# sb-sonata-led.net
KiCad netlist of a schematic drawn in Altium Designer
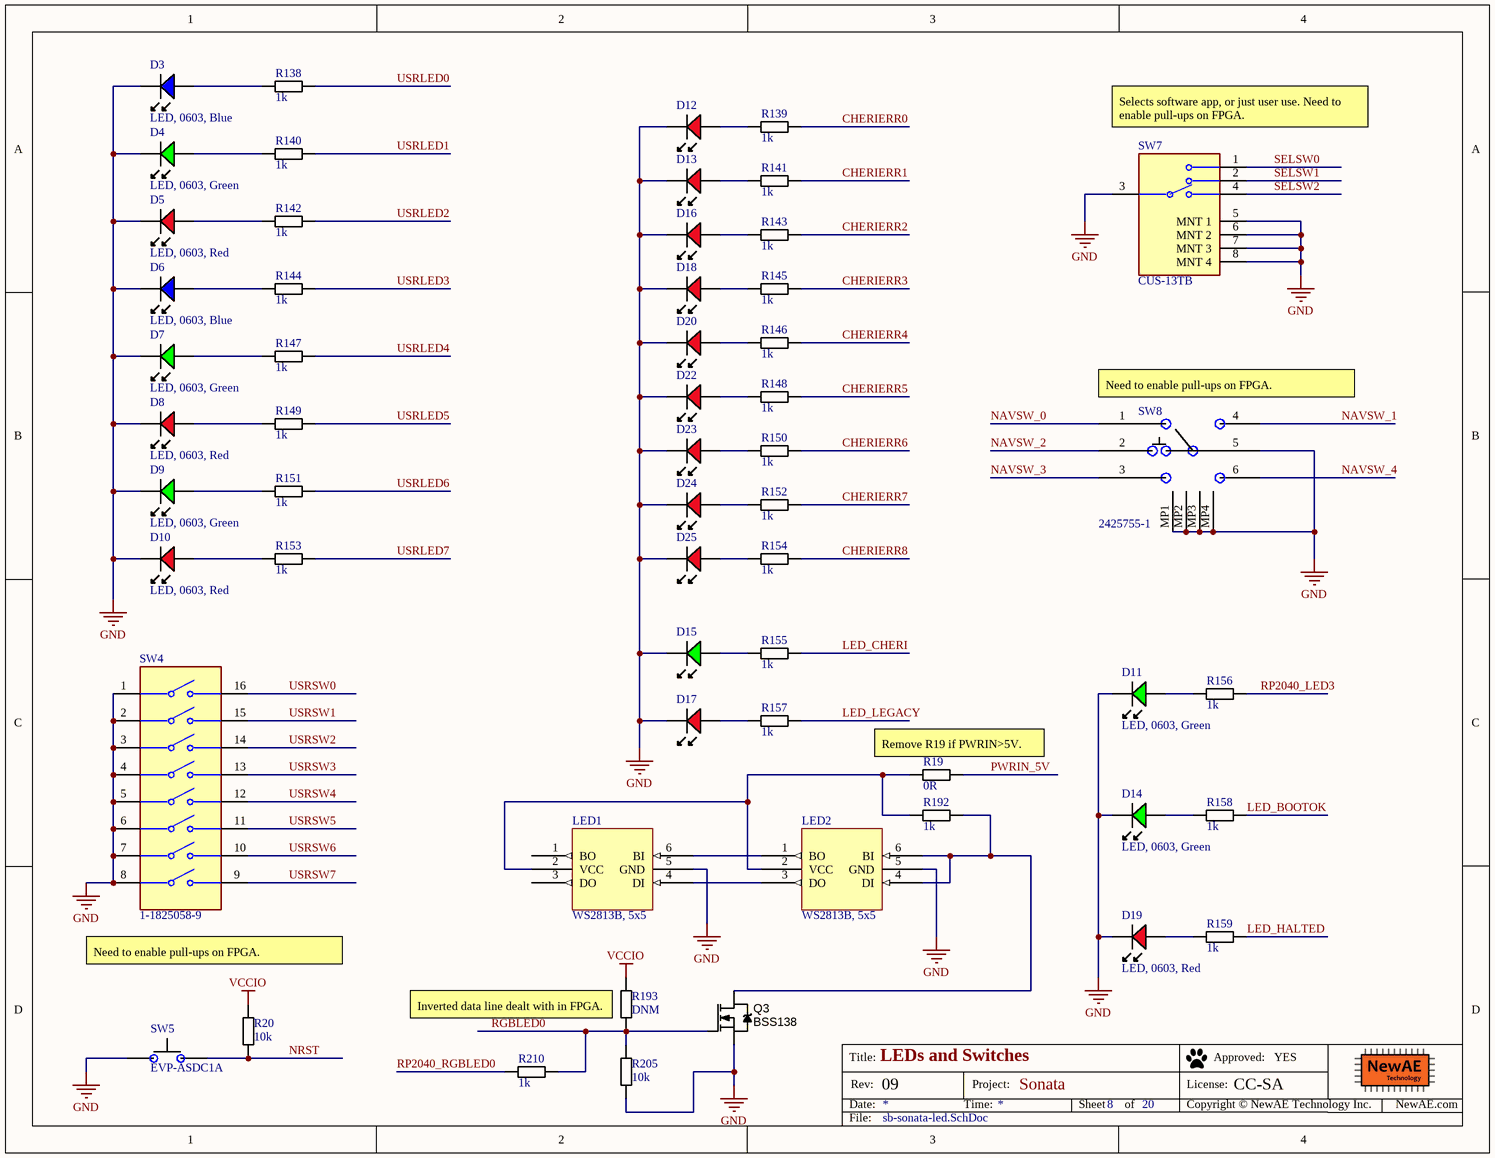
[diagram p0: sb-sonata-led.SchDoc]

(export (version "E")
  (design (tool "Eeschema 10.0.6"))
  (components
    (comp (ref "D3")
      (value "LED, 0603, Blue")
      (footprint "LED-0603-BLUE")
      (description "Chip LED, Blue")
      (fields (field (name "PART NUMBER") "LEDCHIP_0603_BLUE"))
      (libsource (lib "NewAE_AltiumLib") (part "LED_BLUE"))
    )
    (comp (ref "D4")
      (value "LED, 0603, Green")
      (footprint "LED-0603-GREEN")
      (description "Chip LED, Green")
      (fields (field (name "PART NUMBER") "LEDCHIP_0603_GREEN"))
      (libsource (lib "NewAE_AltiumLib") (part "LED_GREEN"))
    )
    (comp (ref "D5")
      (value "LED, 0603, Red")
      (footprint "LED-0603-RED")
      (description "Chip LED, Red")
      (fields (field (name "PART NUMBER") "LEDCHIP_0603_RED"))
      (libsource (lib "NewAE_AltiumLib") (part "LED_RED"))
    )
    (comp (ref "D6")
      (value "LED, 0603, Blue")
      (footprint "LED-0603-BLUE")
      (description "Chip LED, Blue")
      (fields (field (name "PART NUMBER") "LEDCHIP_0603_BLUE"))
      (libsource (lib "NewAE_AltiumLib") (part "LED_BLUE"))
    )
    (comp (ref "D7")
      (value "LED, 0603, Green")
      (footprint "LED-0603-GREEN")
      (description "Chip LED, Green")
      (fields (field (name "PART NUMBER") "LEDCHIP_0603_GREEN"))
      (libsource (lib "NewAE_AltiumLib") (part "LED_GREEN"))
    )
    (comp (ref "D8")
      (value "LED, 0603, Red")
      (footprint "LED-0603-RED")
      (description "Chip LED, Red")
      (fields (field (name "PART NUMBER") "LEDCHIP_0603_RED"))
      (libsource (lib "NewAE_AltiumLib") (part "LED_RED"))
    )
    (comp (ref "D9")
      (value "LED, 0603, Green")
      (footprint "LED-0603-GREEN")
      (description "Chip LED, Green")
      (fields (field (name "PART NUMBER") "LEDCHIP_0603_GREEN"))
      (libsource (lib "NewAE_AltiumLib") (part "LED_GREEN"))
    )
    (comp (ref "D10")
      (value "LED, 0603, Red")
      (footprint "LED-0603-RED")
      (description "Chip LED, Red")
      (fields (field (name "PART NUMBER") "LEDCHIP_0603_RED"))
      (libsource (lib "NewAE_AltiumLib") (part "LED_RED"))
    )
    (comp (ref "D11")
      (value "LED, 0603, Green")
      (footprint "LED-0603-GREEN")
      (description "Chip LED, Green")
      (fields (field (name "PART NUMBER") "LEDCHIP_0603_GREEN"))
      (libsource (lib "NewAE_AltiumLib") (part "LED_GREEN"))
    )
    (comp (ref "D12")
      (value "LED, 0603, Red")
      (footprint "LED-0603-RED")
      (description "Chip LED, Red")
      (fields (field (name "PART NUMBER") "LEDCHIP_0603_RED"))
      (libsource (lib "NewAE_AltiumLib") (part "LED_RED"))
    )
    (comp (ref "D13")
      (value "LED, 0603, Red")
      (footprint "LED-0603-RED")
      (description "Chip LED, Red")
      (fields (field (name "PART NUMBER") "LEDCHIP_0603_RED"))
      (libsource (lib "NewAE_AltiumLib") (part "LED_RED"))
    )
    (comp (ref "D14")
      (value "LED, 0603, Green")
      (footprint "LED-0603-GREEN")
      (description "Chip LED, Green")
      (fields (field (name "PART NUMBER") "LEDCHIP_0603_GREEN"))
      (libsource (lib "NewAE_AltiumLib") (part "LED_GREEN"))
    )
    (comp (ref "D15")
      (value "LED, 0603, Green")
      (footprint "LED-0603-GREEN")
      (description "Chip LED, Green")
      (fields (field (name "PART NUMBER") "LEDCHIP_0603_GREEN"))
      (libsource (lib "NewAE_AltiumLib") (part "LED_GREEN"))
    )
    (comp (ref "D16")
      (value "LED, 0603, Red")
      (footprint "LED-0603-RED")
      (description "Chip LED, Red")
      (fields (field (name "PART NUMBER") "LEDCHIP_0603_RED"))
      (libsource (lib "NewAE_AltiumLib") (part "LED_RED"))
    )
    (comp (ref "D17")
      (value "LED, 0603, Red")
      (footprint "LED-0603-RED")
      (description "Chip LED, Red")
      (fields (field (name "PART NUMBER") "LEDCHIP_0603_RED"))
      (libsource (lib "NewAE_AltiumLib") (part "LED_RED"))
    )
    (comp (ref "D18")
      (value "LED, 0603, Red")
      (footprint "LED-0603-RED")
      (description "Chip LED, Red")
      (fields (field (name "PART NUMBER") "LEDCHIP_0603_RED"))
      (libsource (lib "NewAE_AltiumLib") (part "LED_RED"))
    )
    (comp (ref "D19")
      (value "LED, 0603, Red")
      (footprint "LED-0603-RED")
      (description "Chip LED, Red")
      (fields (field (name "PART NUMBER") "LEDCHIP_0603_RED"))
      (libsource (lib "NewAE_AltiumLib") (part "LED_RED"))
    )
    (comp (ref "D20")
      (value "LED, 0603, Red")
      (footprint "LED-0603-RED")
      (description "Chip LED, Red")
      (fields (field (name "PART NUMBER") "LEDCHIP_0603_RED"))
      (libsource (lib "NewAE_AltiumLib") (part "LED_RED"))
    )
    (comp (ref "D22")
      (value "LED, 0603, Red")
      (footprint "LED-0603-RED")
      (description "Chip LED, Red")
      (fields (field (name "PART NUMBER") "LEDCHIP_0603_RED"))
      (libsource (lib "NewAE_AltiumLib") (part "LED_RED"))
    )
    (comp (ref "D23")
      (value "LED, 0603, Red")
      (footprint "LED-0603-RED")
      (description "Chip LED, Red")
      (fields (field (name "PART NUMBER") "LEDCHIP_0603_RED"))
      (libsource (lib "NewAE_AltiumLib") (part "LED_RED"))
    )
    (comp (ref "D24")
      (value "LED, 0603, Red")
      (footprint "LED-0603-RED")
      (description "Chip LED, Red")
      (fields (field (name "PART NUMBER") "LEDCHIP_0603_RED"))
      (libsource (lib "NewAE_AltiumLib") (part "LED_RED"))
    )
    (comp (ref "D25")
      (value "LED, 0603, Red")
      (footprint "LED-0603-RED")
      (description "Chip LED, Red")
      (fields (field (name "PART NUMBER") "LEDCHIP_0603_RED"))
      (libsource (lib "NewAE_AltiumLib") (part "LED_RED"))
    )
    (comp (ref "LED1")
      (value "WS2813B, 5x5")
      (footprint "WS2813B_5x5")
      (description "WS2813B, 5x5 SMD Neopixel")
      (fields (field (name "PART NUMBER") "WS2813B_5x5"))
      (libsource (lib "NewAE_AltiumLib") (part "WS2813B"))
    )
    (comp (ref "LED2")
      (value "WS2813B, 5x5")
      (footprint "WS2813B_5x5")
      (description "WS2813B, 5x5 SMD Neopixel")
      (fields (field (name "PART NUMBER") "WS2813B_5x5"))
      (libsource (lib "NewAE_AltiumLib") (part "WS2813B"))
    )
    (comp (ref "Q3")
      (value "BSS138")
      (footprint "SOT95P245X110-3M")
      (description "MOSFET N-CH 30V 2.2A SOT23-3")
      (libsource (lib "NewAE_AltiumLib") (part "MOSFET_N_GSD"))
    )
    (comp (ref "R19")
      (value "0R")
      (footprint "RESC1608X55N")
      (description "0R, 0603, 1/10W")
      (fields (field (name "PART NUMBER") "RCHIP-0R-0603") (field (name "TOLERANCE") "1%"))
      (libsource (lib "") (part "RES-EU_1"))
    )
    (comp (ref "R20")
      (value "10k")
      (footprint "RESC1005X40N")
      (description "10k res, 0402, 1%, 1/16W")
      (fields (field (name "PART NUMBER") "RCHIP-10K-0402") (field (name "TOLERANCE") "1%"))
      (libsource (lib "") (part "RES-EU_2"))
    )
    (comp (ref "R138")
      (value "1k")
      (footprint "RESC1005X40N")
      (description "1k res, 0402, 1%, 1/16W")
      (fields (field (name "PART NUMBER") "RCHIP-1K-0402") (field (name "TOLERANCE") "1%"))
      (libsource (lib "NewAE_AltiumLib") (part "RES-EU"))
    )
    (comp (ref "R139")
      (value "1k")
      (footprint "RESC1005X40N")
      (description "1k res, 0402, 1%, 1/16W")
      (fields (field (name "PART NUMBER") "RCHIP-1K-0402") (field (name "TOLERANCE") "1%"))
      (libsource (lib "NewAE_AltiumLib") (part "RES-EU"))
    )
    (comp (ref "R140")
      (value "1k")
      (footprint "RESC1005X40N")
      (description "1k res, 0402, 1%, 1/16W")
      (fields (field (name "PART NUMBER") "RCHIP-1K-0402") (field (name "TOLERANCE") "1%"))
      (libsource (lib "NewAE_AltiumLib") (part "RES-EU"))
    )
    (comp (ref "R141")
      (value "1k")
      (footprint "RESC1005X40N")
      (description "1k res, 0402, 1%, 1/16W")
      (fields (field (name "PART NUMBER") "RCHIP-1K-0402") (field (name "TOLERANCE") "1%"))
      (libsource (lib "NewAE_AltiumLib") (part "RES-EU"))
    )
    (comp (ref "R142")
      (value "1k")
      (footprint "RESC1005X40N")
      (description "1k res, 0402, 1%, 1/16W")
      (fields (field (name "PART NUMBER") "RCHIP-1K-0402") (field (name "TOLERANCE") "1%"))
      (libsource (lib "NewAE_AltiumLib") (part "RES-EU"))
    )
    (comp (ref "R143")
      (value "1k")
      (footprint "RESC1005X40N")
      (description "1k res, 0402, 1%, 1/16W")
      (fields (field (name "PART NUMBER") "RCHIP-1K-0402") (field (name "TOLERANCE") "1%"))
      (libsource (lib "NewAE_AltiumLib") (part "RES-EU"))
    )
    (comp (ref "R144")
      (value "1k")
      (footprint "RESC1005X40N")
      (description "1k res, 0402, 1%, 1/16W")
      (fields (field (name "PART NUMBER") "RCHIP-1K-0402") (field (name "TOLERANCE") "1%"))
      (libsource (lib "NewAE_AltiumLib") (part "RES-EU"))
    )
    (comp (ref "R145")
      (value "1k")
      (footprint "RESC1005X40N")
      (description "1k res, 0402, 1%, 1/16W")
      (fields (field (name "PART NUMBER") "RCHIP-1K-0402") (field (name "TOLERANCE") "1%"))
      (libsource (lib "NewAE_AltiumLib") (part "RES-EU"))
    )
    (comp (ref "R146")
      (value "1k")
      (footprint "RESC1005X40N")
      (description "1k res, 0402, 1%, 1/16W")
      (fields (field (name "PART NUMBER") "RCHIP-1K-0402") (field (name "TOLERANCE") "1%"))
      (libsource (lib "NewAE_AltiumLib") (part "RES-EU"))
    )
    (comp (ref "R147")
      (value "1k")
      (footprint "RESC1005X40N")
      (description "1k res, 0402, 1%, 1/16W")
      (fields (field (name "PART NUMBER") "RCHIP-1K-0402") (field (name "TOLERANCE") "1%"))
      (libsource (lib "NewAE_AltiumLib") (part "RES-EU"))
    )
    (comp (ref "R148")
      (value "1k")
      (footprint "RESC1005X40N")
      (description "1k res, 0402, 1%, 1/16W")
      (fields (field (name "PART NUMBER") "RCHIP-1K-0402") (field (name "TOLERANCE") "1%"))
      (libsource (lib "NewAE_AltiumLib") (part "RES-EU"))
    )
    (comp (ref "R149")
      (value "1k")
      (footprint "RESC1005X40N")
      (description "1k res, 0402, 1%, 1/16W")
      (fields (field (name "PART NUMBER") "RCHIP-1K-0402") (field (name "TOLERANCE") "1%"))
      (libsource (lib "NewAE_AltiumLib") (part "RES-EU"))
    )
    (comp (ref "R150")
      (value "1k")
      (footprint "RESC1005X40N")
      (description "1k res, 0402, 1%, 1/16W")
      (fields (field (name "PART NUMBER") "RCHIP-1K-0402") (field (name "TOLERANCE") "1%"))
      (libsource (lib "NewAE_AltiumLib") (part "RES-EU"))
    )
    (comp (ref "R151")
      (value "1k")
      (footprint "RESC1005X40N")
      (description "1k res, 0402, 1%, 1/16W")
      (fields (field (name "PART NUMBER") "RCHIP-1K-0402") (field (name "TOLERANCE") "1%"))
      (libsource (lib "NewAE_AltiumLib") (part "RES-EU"))
    )
    (comp (ref "R152")
      (value "1k")
      (footprint "RESC1005X40N")
      (description "1k res, 0402, 1%, 1/16W")
      (fields (field (name "PART NUMBER") "RCHIP-1K-0402") (field (name "TOLERANCE") "1%"))
      (libsource (lib "NewAE_AltiumLib") (part "RES-EU"))
    )
    (comp (ref "R153")
      (value "1k")
      (footprint "RESC1005X40N")
      (description "1k res, 0402, 1%, 1/16W")
      (fields (field (name "PART NUMBER") "RCHIP-1K-0402") (field (name "TOLERANCE") "1%"))
      (libsource (lib "NewAE_AltiumLib") (part "RES-EU"))
    )
    (comp (ref "R154")
      (value "1k")
      (footprint "RESC1005X40N")
      (description "1k res, 0402, 1%, 1/16W")
      (fields (field (name "PART NUMBER") "RCHIP-1K-0402") (field (name "TOLERANCE") "1%"))
      (libsource (lib "NewAE_AltiumLib") (part "RES-EU"))
    )
    (comp (ref "R155")
      (value "1k")
      (footprint "RESC1005X40N")
      (description "1k res, 0402, 1%, 1/16W")
      (fields (field (name "PART NUMBER") "RCHIP-1K-0402") (field (name "TOLERANCE") "1%"))
      (libsource (lib "NewAE_AltiumLib") (part "RES-EU"))
    )
    (comp (ref "R156")
      (value "1k")
      (footprint "RESC1005X40N")
      (description "1k res, 0402, 1%, 1/16W")
      (fields (field (name "PART NUMBER") "RCHIP-1K-0402") (field (name "TOLERANCE") "1%"))
      (libsource (lib "NewAE_AltiumLib") (part "RES-EU"))
    )
    (comp (ref "R157")
      (value "1k")
      (footprint "RESC1005X40N")
      (description "1k res, 0402, 1%, 1/16W")
      (fields (field (name "PART NUMBER") "RCHIP-1K-0402") (field (name "TOLERANCE") "1%"))
      (libsource (lib "NewAE_AltiumLib") (part "RES-EU"))
    )
    (comp (ref "R158")
      (value "1k")
      (footprint "RESC1005X40N")
      (description "1k res, 0402, 1%, 1/16W")
      (fields (field (name "PART NUMBER") "RCHIP-1K-0402") (field (name "TOLERANCE") "1%"))
      (libsource (lib "NewAE_AltiumLib") (part "RES-EU"))
    )
    (comp (ref "R159")
      (value "1k")
      (footprint "RESC1005X40N")
      (description "1k res, 0402, 1%, 1/16W")
      (fields (field (name "PART NUMBER") "RCHIP-1K-0402") (field (name "TOLERANCE") "1%"))
      (libsource (lib "NewAE_AltiumLib") (part "RES-EU"))
    )
    (comp (ref "R192")
      (value "1k")
      (footprint "RESC1005X40N")
      (description "1k res, 0402, 1%, 1/16W")
      (fields (field (name "PART NUMBER") "RCHIP-1K-0402") (field (name "TOLERANCE") "1%"))
      (libsource (lib "") (part "RES-EU_1"))
    )
    (comp (ref "R193")
      (value "DNM")
      (footprint "RESC1005X40N")
      (fields (field (name "PART NUMBER") "RCHIP-DNM-0402"))
      (libsource (lib "") (part "RES-EU_2"))
    )
    (comp (ref "R205")
      (value "10k")
      (footprint "RESC1005X40N")
      (description "10k res, 0402, 1%, 1/16W")
      (fields (field (name "PART NUMBER") "RCHIP-10K-0402") (field (name "TOLERANCE") "1%"))
      (libsource (lib "") (part "RES-EU_2"))
    )
    (comp (ref "R210")
      (value "1k")
      (footprint "RESC1005X40N")
      (description "1k res, 0402, 1%, 1/16W")
      (fields (field (name "PART NUMBER") "RCHIP-1K-0402") (field (name "TOLERANCE") "1%"))
      (libsource (lib "NewAE_AltiumLib") (part "RES-EU"))
    )
    (comp (ref "SW4")
      (value "1-1825058-9")
      (footprint "FP-1-1825058-9-MFG")
      (description "SWITCH SLIDE DIP SPST 100MA 24V")
      (fields
        (field (name "MANUFACTURER") "TE Connectivity")
        (field (name "OCTOPART") "https://octopart.com/1-1825058-9-te+connectivity-46507285")
      )
      (libsource (lib "Altium Content Vault") (part "88b473189f0daa5e8e83a09a3141fee"))
    )
    (comp (ref "SW5")
      (value "EVP-ASDC1A")
      (footprint "EVPAS")
      (description "Pushbutton, SMD, 2.5NM force, NO")
      (libsource (lib "NewAE_AltiumLib") (part "SW_PB_NO_2PIN"))
    )
    (comp (ref "SW7")
      (value "CUS-13TB")
      (footprint "FP-CUS-13TB-MFG")
      (description "SWITCH SLIDE SP3T 300MA 4V")
      (libsource (lib "Altium Content Vault") (part "47bcb96ef67674530f45e4053201745"))
    )
    (comp (ref "SW8")
      (value "2425755-1")
      (footprint "2425755-1")
      (description "5-Way Joystick")
      (libsource (lib "NewAE_AltiumLib") (part "SW_5WAY_4MP"))
    )
  )
  (nets
    (net (code "1") (name "/CHERIERR0") (class "Default")
      (node (ref "R139") (pin "1") (pinfunction "1_1") (pintype "passive"))
    )
    (net (code "2") (name "/CHERIERR1") (class "Default")
      (node (ref "R141") (pin "1") (pinfunction "1_1") (pintype "passive"))
    )
    (net (code "3") (name "/CHERIERR2") (class "Default")
      (node (ref "R143") (pin "1") (pinfunction "1_1") (pintype "passive"))
    )
    (net (code "4") (name "/CHERIERR3") (class "Default")
      (node (ref "R145") (pin "1") (pinfunction "1_1") (pintype "passive"))
    )
    (net (code "5") (name "/CHERIERR4") (class "Default")
      (node (ref "R146") (pin "1") (pinfunction "1_1") (pintype "passive"))
    )
    (net (code "6") (name "/CHERIERR5") (class "Default")
      (node (ref "R148") (pin "1") (pinfunction "1_1") (pintype "passive"))
    )
    (net (code "7") (name "/CHERIERR6") (class "Default")
      (node (ref "R150") (pin "1") (pinfunction "1_1") (pintype "passive"))
    )
    (net (code "8") (name "/CHERIERR7") (class "Default")
      (node (ref "R152") (pin "1") (pinfunction "1_1") (pintype "passive"))
    )
    (net (code "9") (name "/CHERIERR8") (class "Default")
      (node (ref "R154") (pin "1") (pinfunction "1_1") (pintype "passive"))
    )
    (net (code "10") (name "/LED_BOOTOK") (class "Default")
      (node (ref "R158") (pin "1") (pinfunction "1_1") (pintype "passive"))
    )
    (net (code "11") (name "/LED_CHERI") (class "Default")
      (node (ref "R155") (pin "1") (pinfunction "1_1") (pintype "passive"))
    )
    (net (code "12") (name "/LED_HALTED") (class "Default")
      (node (ref "R159") (pin "1") (pinfunction "1_1") (pintype "passive"))
    )
    (net (code "13") (name "/LED_LEGACY") (class "Default")
      (node (ref "R157") (pin "1") (pinfunction "1_1") (pintype "passive"))
    )
    (net (code "14") (name "/NAVSW_0") (class "Default")
      (node (ref "SW8") (pin "1") (pinfunction "1_1") (pintype "passive"))
    )
    (net (code "15") (name "/NAVSW_1") (class "Default")
      (node (ref "SW8") (pin "4") (pinfunction "4_4") (pintype "passive"))
    )
    (net (code "16") (name "/NAVSW_2") (class "Default")
      (node (ref "SW8") (pin "2") (pinfunction "2_2") (pintype "passive"))
    )
    (net (code "17") (name "/NAVSW_3") (class "Default")
      (node (ref "SW8") (pin "3") (pinfunction "3_3") (pintype "passive"))
    )
    (net (code "18") (name "/NAVSW_4") (class "Default")
      (node (ref "SW8") (pin "6") (pinfunction "6_6") (pintype "passive"))
    )
    (net (code "19") (name "/NRST") (class "Default")
      (node (ref "R20") (pin "2") (pinfunction "2_2") (pintype "passive"))
      (node (ref "SW5") (pin "2") (pinfunction "IN_2") (pintype "passive"))
    )
    (net (code "20") (name "/PWRIN_5V") (class "Default")
      (node (ref "R19") (pin "2") (pinfunction "2_2") (pintype "passive"))
    )
    (net (code "21") (name "/RGBLED0") (class "Default")
      (node (ref "Q3") (pin "1") (pinfunction "G_1") (pintype "passive"))
      (node (ref "R193") (pin "2") (pinfunction "2_2") (pintype "passive"))
      (node (ref "R205") (pin "1") (pinfunction "1_1") (pintype "passive"))
      (node (ref "R210") (pin "1") (pinfunction "1_1") (pintype "passive"))
    )
    (net (code "22") (name "/RP2040_LED3") (class "Default")
      (node (ref "R156") (pin "1") (pinfunction "1_1") (pintype "passive"))
    )
    (net (code "23") (name "/RP2040_RGBLED0") (class "Default")
      (node (ref "R210") (pin "2") (pinfunction "2_2") (pintype "passive"))
    )
    (net (code "24") (name "/SELSW0") (class "Default")
      (node (ref "SW7") (pin "1") (pinfunction "1_1") (pintype "passive"))
    )
    (net (code "25") (name "/SELSW1") (class "Default")
      (node (ref "SW7") (pin "2") (pinfunction "2_2") (pintype "passive"))
    )
    (net (code "26") (name "/SELSW2") (class "Default")
      (node (ref "SW7") (pin "4") (pinfunction "4_4") (pintype "passive"))
    )
    (net (code "27") (name "/USRLED0") (class "Default")
      (node (ref "R138") (pin "1") (pinfunction "1_1") (pintype "passive"))
    )
    (net (code "28") (name "/USRLED1") (class "Default")
      (node (ref "R140") (pin "1") (pinfunction "1_1") (pintype "passive"))
    )
    (net (code "29") (name "/USRLED2") (class "Default")
      (node (ref "R142") (pin "1") (pinfunction "1_1") (pintype "passive"))
    )
    (net (code "30") (name "/USRLED3") (class "Default")
      (node (ref "R144") (pin "1") (pinfunction "1_1") (pintype "passive"))
    )
    (net (code "31") (name "/USRLED4") (class "Default")
      (node (ref "R147") (pin "1") (pinfunction "1_1") (pintype "passive"))
    )
    (net (code "32") (name "/USRLED5") (class "Default")
      (node (ref "R149") (pin "1") (pinfunction "1_1") (pintype "passive"))
    )
    (net (code "33") (name "/USRLED6") (class "Default")
      (node (ref "R151") (pin "1") (pinfunction "1_1") (pintype "passive"))
    )
    (net (code "34") (name "/USRLED7") (class "Default")
      (node (ref "R153") (pin "1") (pinfunction "1_1") (pintype "passive"))
    )
    (net (code "35") (name "/USRSW0") (class "Default")
      (node (ref "SW4") (pin "16") (pinfunction "16_16") (pintype "passive"))
    )
    (net (code "36") (name "/USRSW1") (class "Default")
      (node (ref "SW4") (pin "15") (pinfunction "15_15") (pintype "passive"))
    )
    (net (code "37") (name "/USRSW2") (class "Default")
      (node (ref "SW4") (pin "14") (pinfunction "14_14") (pintype "passive"))
    )
    (net (code "38") (name "/USRSW3") (class "Default")
      (node (ref "SW4") (pin "13") (pinfunction "13_13") (pintype "passive"))
    )
    (net (code "39") (name "/USRSW4") (class "Default")
      (node (ref "SW4") (pin "12") (pinfunction "12_12") (pintype "passive"))
    )
    (net (code "40") (name "/USRSW5") (class "Default")
      (node (ref "SW4") (pin "11") (pinfunction "11_11") (pintype "passive"))
    )
    (net (code "41") (name "/USRSW6") (class "Default")
      (node (ref "SW4") (pin "10") (pinfunction "10_10") (pintype "passive"))
    )
    (net (code "42") (name "/USRSW7") (class "Default")
      (node (ref "SW4") (pin "9") (pinfunction "9_9") (pintype "passive"))
    )
    (net (code "43") (name "GND") (class "Default")
      (node (ref "D10") (pin "K") (pinfunction "K_K") (pintype "passive"))
      (node (ref "D11") (pin "K") (pinfunction "K_K") (pintype "passive"))
      (node (ref "D12") (pin "K") (pinfunction "K_K") (pintype "passive"))
      (node (ref "D13") (pin "K") (pinfunction "K_K") (pintype "passive"))
      (node (ref "D14") (pin "K") (pinfunction "K_K") (pintype "passive"))
      (node (ref "D15") (pin "K") (pinfunction "K_K") (pintype "passive"))
      (node (ref "D16") (pin "K") (pinfunction "K_K") (pintype "passive"))
      (node (ref "D17") (pin "K") (pinfunction "K_K") (pintype "passive"))
      (node (ref "D18") (pin "K") (pinfunction "K_K") (pintype "passive"))
      (node (ref "D19") (pin "K") (pinfunction "K_K") (pintype "passive"))
      (node (ref "D20") (pin "K") (pinfunction "K_K") (pintype "passive"))
      (node (ref "D22") (pin "K") (pinfunction "K_K") (pintype "passive"))
      (node (ref "D23") (pin "K") (pinfunction "K_K") (pintype "passive"))
      (node (ref "D24") (pin "K") (pinfunction "K_K") (pintype "passive"))
      (node (ref "D25") (pin "K") (pinfunction "K_K") (pintype "passive"))
      (node (ref "D3") (pin "K") (pinfunction "K_K") (pintype "passive"))
      (node (ref "D4") (pin "K") (pinfunction "K_K") (pintype "passive"))
      (node (ref "D5") (pin "K") (pinfunction "K_K") (pintype "passive"))
      (node (ref "D6") (pin "K") (pinfunction "K_K") (pintype "passive"))
      (node (ref "D7") (pin "K") (pinfunction "K_K") (pintype "passive"))
      (node (ref "D8") (pin "K") (pinfunction "K_K") (pintype "passive"))
      (node (ref "D9") (pin "K") (pinfunction "K_K") (pintype "passive"))
      (node (ref "LED1") (pin "5") (pinfunction "GND_5") (pintype "passive"))
      (node (ref "LED2") (pin "5") (pinfunction "GND_5") (pintype "passive"))
      (node (ref "Q3") (pin "2") (pinfunction "S_2") (pintype "passive"))
      (node (ref "R205") (pin "2") (pinfunction "2_2") (pintype "passive"))
      (node (ref "SW4") (pin "1") (pinfunction "1_1") (pintype "passive"))
      (node (ref "SW4") (pin "2") (pinfunction "2_2") (pintype "passive"))
      (node (ref "SW4") (pin "3") (pinfunction "3_3") (pintype "passive"))
      (node (ref "SW4") (pin "4") (pinfunction "4_4") (pintype "passive"))
      (node (ref "SW4") (pin "5") (pinfunction "5_5") (pintype "passive"))
      (node (ref "SW4") (pin "6") (pinfunction "6_6") (pintype "passive"))
      (node (ref "SW4") (pin "7") (pinfunction "7_7") (pintype "passive"))
      (node (ref "SW4") (pin "8") (pinfunction "8_8") (pintype "passive"))
      (node (ref "SW5") (pin "1") (pinfunction "IN_1") (pintype "passive"))
      (node (ref "SW7") (pin "3") (pinfunction "C_3") (pintype "passive"))
      (node (ref "SW7") (pin "5") (pinfunction "MNT_1_5") (pintype "passive"))
      (node (ref "SW7") (pin "6") (pinfunction "MNT_2_6") (pintype "passive"))
      (node (ref "SW7") (pin "7") (pinfunction "MNT_3_7") (pintype "passive"))
      (node (ref "SW7") (pin "8") (pinfunction "MNT_4_8") (pintype "passive"))
      (node (ref "SW8") (pin "5") (pinfunction "5_5") (pintype "passive"))
      (node (ref "SW8") (pin "MP1") (pinfunction "MP1_MP1") (pintype "passive"))
      (node (ref "SW8") (pin "MP2") (pinfunction "MP2_MP2") (pintype "passive"))
      (node (ref "SW8") (pin "MP3") (pinfunction "MP3_MP3") (pintype "passive"))
      (node (ref "SW8") (pin "MP4") (pinfunction "MP4_MP4") (pintype "passive"))
    )
    (net (code "44") (name "Net-(D3-PadA)") (class "Default")
      (node (ref "D3") (pin "A") (pinfunction "A_A") (pintype "passive"))
      (node (ref "R138") (pin "2") (pinfunction "2_2") (pintype "passive"))
    )
    (net (code "45") (name "Net-(D4-PadA)") (class "Default")
      (node (ref "D4") (pin "A") (pinfunction "A_A") (pintype "passive"))
      (node (ref "R140") (pin "2") (pinfunction "2_2") (pintype "passive"))
    )
    (net (code "46") (name "Net-(D5-PadA)") (class "Default")
      (node (ref "D5") (pin "A") (pinfunction "A_A") (pintype "passive"))
      (node (ref "R142") (pin "2") (pinfunction "2_2") (pintype "passive"))
    )
    (net (code "47") (name "Net-(D6-PadA)") (class "Default")
      (node (ref "D6") (pin "A") (pinfunction "A_A") (pintype "passive"))
      (node (ref "R144") (pin "2") (pinfunction "2_2") (pintype "passive"))
    )
    (net (code "48") (name "Net-(D7-PadA)") (class "Default")
      (node (ref "D7") (pin "A") (pinfunction "A_A") (pintype "passive"))
      (node (ref "R147") (pin "2") (pinfunction "2_2") (pintype "passive"))
    )
    (net (code "49") (name "Net-(D8-PadA)") (class "Default")
      (node (ref "D8") (pin "A") (pinfunction "A_A") (pintype "passive"))
      (node (ref "R149") (pin "2") (pinfunction "2_2") (pintype "passive"))
    )
    (net (code "50") (name "Net-(D9-PadA)") (class "Default")
      (node (ref "D9") (pin "A") (pinfunction "A_A") (pintype "passive"))
      (node (ref "R151") (pin "2") (pinfunction "2_2") (pintype "passive"))
    )
    (net (code "51") (name "Net-(D10-PadA)") (class "Default")
      (node (ref "D10") (pin "A") (pinfunction "A_A") (pintype "passive"))
      (node (ref "R153") (pin "2") (pinfunction "2_2") (pintype "passive"))
    )
    (net (code "52") (name "Net-(D11-PadA)") (class "Default")
      (node (ref "D11") (pin "A") (pinfunction "A_A") (pintype "passive"))
      (node (ref "R156") (pin "2") (pinfunction "2_2") (pintype "passive"))
    )
    (net (code "53") (name "Net-(D12-PadA)") (class "Default")
      (node (ref "D12") (pin "A") (pinfunction "A_A") (pintype "passive"))
      (node (ref "R139") (pin "2") (pinfunction "2_2") (pintype "passive"))
    )
    (net (code "54") (name "Net-(D13-PadA)") (class "Default")
      (node (ref "D13") (pin "A") (pinfunction "A_A") (pintype "passive"))
      (node (ref "R141") (pin "2") (pinfunction "2_2") (pintype "passive"))
    )
    (net (code "55") (name "Net-(D14-PadA)") (class "Default")
      (node (ref "D14") (pin "A") (pinfunction "A_A") (pintype "passive"))
      (node (ref "R158") (pin "2") (pinfunction "2_2") (pintype "passive"))
    )
    (net (code "56") (name "Net-(D15-PadA)") (class "Default")
      (node (ref "D15") (pin "A") (pinfunction "A_A") (pintype "passive"))
      (node (ref "R155") (pin "2") (pinfunction "2_2") (pintype "passive"))
    )
    (net (code "57") (name "Net-(D16-PadA)") (class "Default")
      (node (ref "D16") (pin "A") (pinfunction "A_A") (pintype "passive"))
      (node (ref "R143") (pin "2") (pinfunction "2_2") (pintype "passive"))
    )
    (net (code "58") (name "Net-(D17-PadA)") (class "Default")
      (node (ref "D17") (pin "A") (pinfunction "A_A") (pintype "passive"))
      (node (ref "R157") (pin "2") (pinfunction "2_2") (pintype "passive"))
    )
    (net (code "59") (name "Net-(D18-PadA)") (class "Default")
      (node (ref "D18") (pin "A") (pinfunction "A_A") (pintype "passive"))
      (node (ref "R145") (pin "2") (pinfunction "2_2") (pintype "passive"))
    )
    (net (code "60") (name "Net-(D19-PadA)") (class "Default")
      (node (ref "D19") (pin "A") (pinfunction "A_A") (pintype "passive"))
      (node (ref "R159") (pin "2") (pinfunction "2_2") (pintype "passive"))
    )
    (net (code "61") (name "Net-(D20-PadA)") (class "Default")
      (node (ref "D20") (pin "A") (pinfunction "A_A") (pintype "passive"))
      (node (ref "R146") (pin "2") (pinfunction "2_2") (pintype "passive"))
    )
    (net (code "62") (name "Net-(D22-PadA)") (class "Default")
      (node (ref "D22") (pin "A") (pinfunction "A_A") (pintype "passive"))
      (node (ref "R148") (pin "2") (pinfunction "2_2") (pintype "passive"))
    )
    (net (code "63") (name "Net-(D23-PadA)") (class "Default")
      (node (ref "D23") (pin "A") (pinfunction "A_A") (pintype "passive"))
      (node (ref "R150") (pin "2") (pinfunction "2_2") (pintype "passive"))
    )
    (net (code "64") (name "Net-(D24-PadA)") (class "Default")
      (node (ref "D24") (pin "A") (pinfunction "A_A") (pintype "passive"))
      (node (ref "R152") (pin "2") (pinfunction "2_2") (pintype "passive"))
    )
    (net (code "65") (name "Net-(D25-PadA)") (class "Default")
      (node (ref "D25") (pin "A") (pinfunction "A_A") (pintype "passive"))
      (node (ref "R154") (pin "2") (pinfunction "2_2") (pintype "passive"))
    )
    (net (code "66") (name "Net-(LED1-BI)") (class "Default")
      (node (ref "LED1") (pin "6") (pinfunction "BI_6") (pintype "input"))
      (node (ref "LED2") (pin "1") (pinfunction "BO_1") (pintype "output"))
    )
    (net (code "67") (name "Net-(LED1-DI)") (class "Default")
      (node (ref "LED1") (pin "4") (pinfunction "DI_4") (pintype "input"))
      (node (ref "LED2") (pin "3") (pinfunction "DO_3") (pintype "output"))
    )
    (net (code "68") (name "Net-(LED1-VCC)") (class "Default")
      (node (ref "LED1") (pin "2") (pinfunction "VCC_2") (pintype "passive"))
      (node (ref "LED2") (pin "2") (pinfunction "VCC_2") (pintype "passive"))
      (node (ref "R19") (pin "1") (pinfunction "1_1") (pintype "passive"))
      (node (ref "R192") (pin "1") (pinfunction "1_1") (pintype "passive"))
    )
    (net (code "69") (name "Net-(LED2-BI)") (class "Default")
      (node (ref "LED2") (pin "4") (pinfunction "DI_4") (pintype "input"))
      (node (ref "LED2") (pin "6") (pinfunction "BI_6") (pintype "input"))
      (node (ref "Q3") (pin "3") (pinfunction "D_3") (pintype "passive"))
      (node (ref "R192") (pin "2") (pinfunction "2_2") (pintype "passive"))
    )
    (net (code "70") (name "VCCIO") (class "Default")
      (node (ref "R193") (pin "1") (pinfunction "1_1") (pintype "passive"))
      (node (ref "R20") (pin "1") (pinfunction "1_1") (pintype "passive"))
    )
    (net (code "71") (name "unconnected-(LED1-BO-Pad1)") (class "Default")
      (node (ref "LED1") (pin "1") (pinfunction "BO_1") (pintype "output"))
    )
    (net (code "72") (name "unconnected-(LED1-DO-Pad3)") (class "Default")
      (node (ref "LED1") (pin "3") (pinfunction "DO_3") (pintype "output"))
    )
  )
)
